# LB_BIT_o13_FAN-v02_rev1.net
KiCad netlist of a schematic drawn in EAGLE
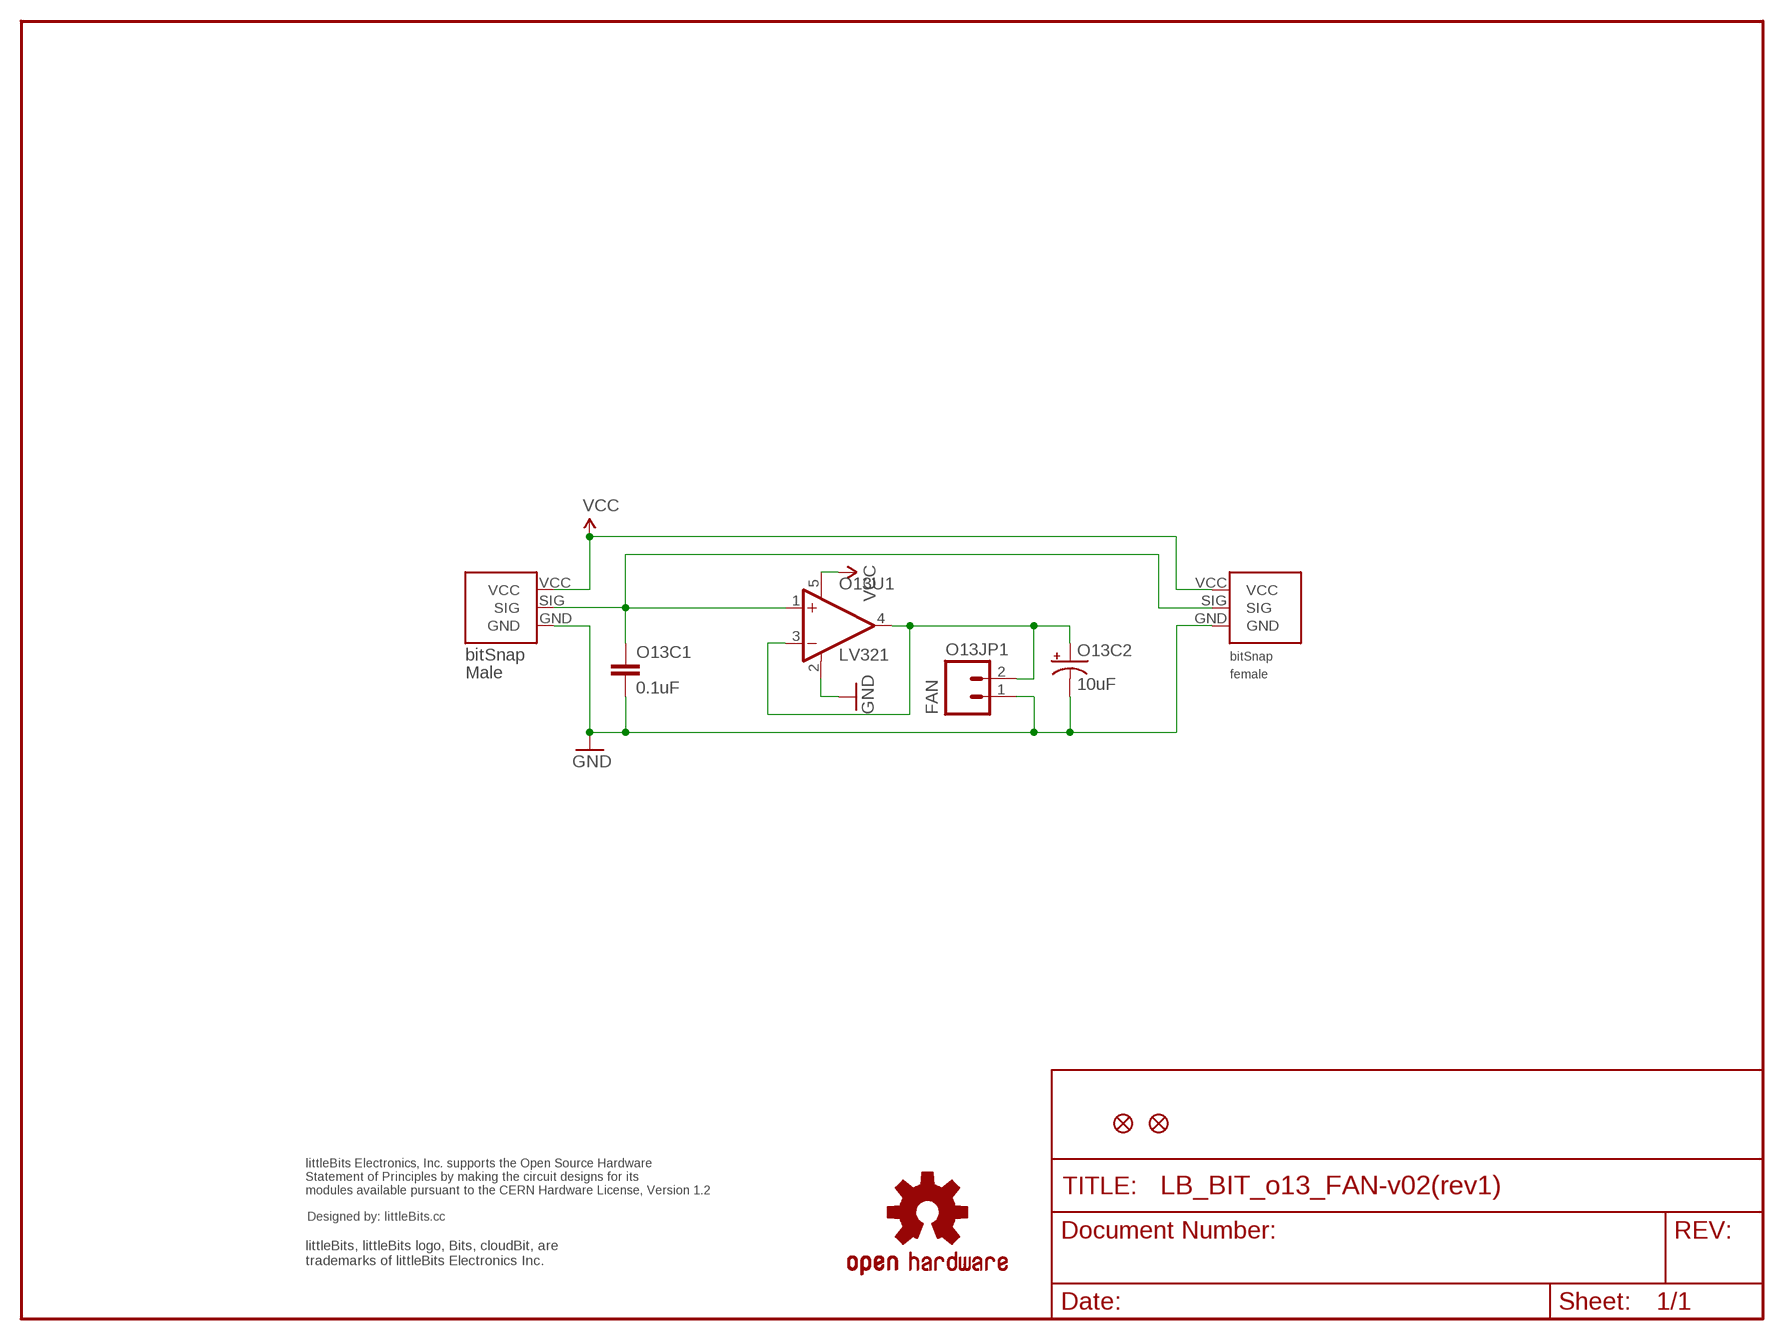
[diagram p0: schematic, sheet 1]

(export (version "E")
  (design (tool "Eeschema 10.0.6"))
  (components
    (comp (ref "JP2")
      (value "FIDUCIAL1X2")
      (footprint "eagle-import:FIDUCIAL-1X2")
      (libsource (lib "eagle-import") (part "FIDUCIAL1X2"))
    )
    (comp (ref "JP3")
      (value "FIDUCIAL1X2")
      (footprint "eagle-import:FIDUCIAL-1X2")
      (libsource (lib "eagle-import") (part "FIDUCIAL1X2"))
    )
    (comp (ref "O13BSF")
      (value "BITSNAP_FEMALE")
      (footprint "eagle-import:BITSNAP_FEMALE")
      (libsource (lib "eagle-import") (part "BITSNAP_FEMALE"))
    )
    (comp (ref "O13BSM")
      (value "BITSNAP_MALE")
      (footprint "eagle-import:BITSNAP_MALE")
      (libsource (lib "eagle-import") (part "BITSNAP_MALE"))
    )
    (comp (ref "O13C1")
      (value "0.1uF")
      (footprint "eagle-import:0603-CAP")
      (libsource (lib "eagle-import") (part "CAP0603-CAP"))
    )
    (comp (ref "O13C2")
      (value "10uF")
      (footprint "eagle-import:EIA3216")
      (libsource (lib "eagle-import") (part "CAP_POL1206"))
    )
    (comp (ref "O13JP1")
      (value "FAN")
      (footprint "eagle-import:1X02")
      (libsource (lib "eagle-import") (part "M02PTH"))
    )
    (comp (ref "O13U1")
      (value "LV321")
      (footprint "eagle-import:SC70-5")
      (libsource (lib "eagle-import") (part "LV321"))
    )
    (comp (ref "U$1")
      (value "OSHWCREDIT")
      (footprint "eagle-import:OSHWCREDIT")
      (libsource (lib "eagle-import") (part "OSHWCREDIT"))
    )
    (comp (ref "U$5")
      (value "OSHW-LOGOL")
      (footprint "eagle-import:OSHW-LOGO-L")
      (libsource (lib "eagle-import") (part "OSHW-LOGOL"))
    )
  )
  (nets
    (net (code "1") (name "GND") (class "Default")
      (node (ref "O13BSF") (pin "GND") (pinfunction "GND_GND") (pintype "bidirectional"))
      (node (ref "O13BSM") (pin "GND") (pinfunction "GND_GND") (pintype "bidirectional"))
      (node (ref "O13C1") (pin "2") (pinfunction "2_2") (pintype "passive"))
      (node (ref "O13C2") (pin "C") (pinfunction "-_C") (pintype "passive"))
      (node (ref "O13JP1") (pin "1") (pinfunction "1_1") (pintype "passive"))
      (node (ref "O13U1") (pin "2") (pinfunction "V-_2") (pintype "power_in"))
    )
    (net (code "2") (name "Net-(O13C2-+)") (class "Default")
      (node (ref "O13C2") (pin "A") (pinfunction "+_A") (pintype "passive"))
      (node (ref "O13JP1") (pin "2") (pinfunction "2_2") (pintype "passive"))
      (node (ref "O13U1") (pin "3") (pinfunction "-IN_3") (pintype "input"))
      (node (ref "O13U1") (pin "4") (pinfunction "OUT_4") (pintype "output"))
    )
    (net (code "3") (name "Net-(O13U1-+IN)") (class "Default")
      (node (ref "O13BSF") (pin "SIG") (pinfunction "SIG_SIG") (pintype "bidirectional"))
      (node (ref "O13BSM") (pin "SIG") (pinfunction "SIG_SIG") (pintype "bidirectional"))
      (node (ref "O13C1") (pin "1") (pinfunction "1_1") (pintype "passive"))
      (node (ref "O13U1") (pin "1") (pinfunction "+IN_1") (pintype "input"))
    )
    (net (code "4") (name "VCC") (class "Default")
      (node (ref "O13BSF") (pin "VCC") (pinfunction "VCC_VCC") (pintype "bidirectional"))
      (node (ref "O13BSM") (pin "VCC") (pinfunction "VCC_VCC") (pintype "bidirectional"))
      (node (ref "O13U1") (pin "5") (pinfunction "V+_5") (pintype "power_in"))
    )
  )
)
